# Sheet1.net
KiCad netlist of a schematic drawn in Altium Designer
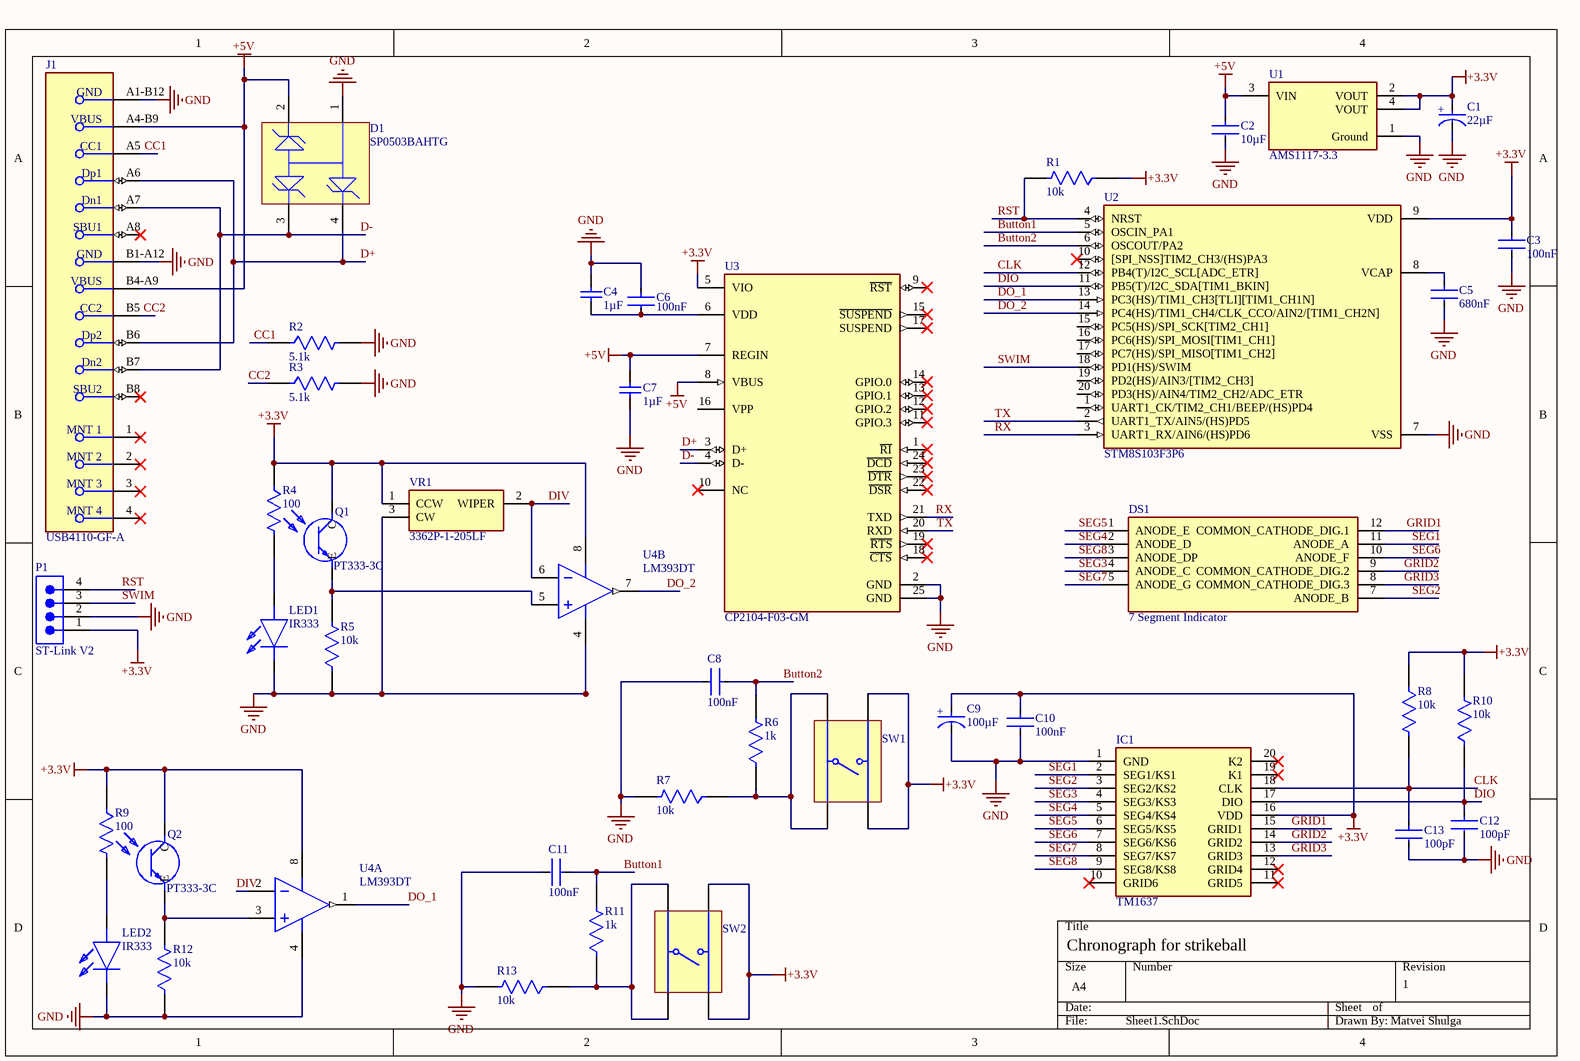
[diagram p0: Sheet1.SchDoc]

(export (version "E")
  (design (tool "Eeschema 10.0.6"))
  (components
    (comp (ref "C1")
      (value "22µF")
      (footprint "FP-TAJA-MFG")
      (description "Cap Tant Solid 22uF 10V A CASE 20%( 3.2 X 1.6 X 1.6mm) Inward L SMD 3216-18 3 Ohm 125C T/R")
      (fields (field (name "VOLTAGE") "10V") (field (name "TOLERANCE") "20%"))
      (libsource (lib "Matvey Shulga") (part "203bc49f2ac43e59fd269a8c329ed05"))
    )
    (comp (ref "C2")
      (value "10µF")
      (footprint "FP-GCJ31C-0_4-IPC_C")
      (description "Ceramic Capacitor, Ceramic, 35V, 10% +Tol, 10% -Tol, X7T, 22/-33% TC, 10uF, Surface Mount, 1206")
      (fields (field (name "VOLTAGE") "35V") (field (name "TOLERANCE") "10%"))
      (libsource (lib "Matvey Shulga") (part "02cd4be3c70576c341d710602a673aa"))
    )
    (comp (ref "C3")
      (value "100nF")
      (footprint "FP-1206-L_3_2_0_15-W_1_6-IPC_B")
      (fields (field (name "Comment") "UMK316B7104KLHT"))
      (libsource (lib "Matvey Shulga") (part "02cd4be3c70576c341d710602a673aa"))
    )
    (comp (ref "C4")
      (value "1µF")
      (footprint "CAPC1206(3216)130_M")
      (fields
        (field (name "VOLTAGE") "10V")
        (field (name "TOLERANCE") "5%")
        (field (name "Comment") "1206ZC105JAT2A")
      )
      (libsource (lib "Matvey Shulga") (part "CAP"))
    )
    (comp (ref "C5")
      (value "680nF")
      (footprint "FP-CC0805-0_85-IPC_A")
      (fields (field (name "Comment") "CC0805KKX7R6BB684"))
      (libsource (lib "Matvey Shulga") (part "11868f565c42a9108669ba33697ecf6"))
    )
    (comp (ref "C6")
      (value "100nF")
      (footprint "FP-1206-L_3_2_0_15-W_1_6-IPC_B")
      (fields (field (name "Comment") "UMK316B7104KLHT"))
      (libsource (lib "Matvey Shulga") (part "02cd4be3c70576c341d710602a673aa"))
    )
    (comp (ref "C7")
      (value "1µF")
      (footprint "CAPC1206(3216)130_M")
      (fields
        (field (name "VOLTAGE") "10V")
        (field (name "TOLERANCE") "5%")
        (field (name "Comment") "1206ZC105JAT2A")
      )
      (libsource (lib "Matvey Shulga") (part "CAP"))
    )
    (comp (ref "C8")
      (value "100nF")
      (footprint "FP-1206-L_3_2_0_15-W_1_6-IPC_B")
      (fields (field (name "Comment") "UMK316B7104KLHT"))
      (libsource (lib "Matvey Shulga") (part "02cd4be3c70576c341d710602a673aa"))
    )
    (comp (ref "C9")
      (value "100µF")
      (footprint "FP-TLJA-MFG")
      (description "Cap Tant Solid 100uF 6.3V A CASE 20% (3.2 X 1.6 X 1.6mm) Inward L SMD 3216-18 0.5 Ohm 125C T/R")
      (fields (field (name "VOLTAGE") "6.3V") (field (name "TOLERANCE") "20%"))
      (libsource (lib "Matvey Shulga") (part "a00bbbee19879c290e62620ae7e47b1"))
    )
    (comp (ref "C10")
      (value "100nF")
      (footprint "FP-1206-L_3_2_0_15-W_1_6-IPC_B")
      (fields (field (name "Comment") "UMK316B7104KLHT"))
      (libsource (lib "Matvey Shulga") (part "02cd4be3c70576c341d710602a673aa"))
    )
    (comp (ref "C11")
      (value "100nF")
      (footprint "FP-1206-L_3_2_0_15-W_1_6-IPC_B")
      (fields (field (name "Comment") "UMK316B7104KLHT"))
      (libsource (lib "Matvey Shulga") (part "02cd4be3c70576c341d710602a673aa"))
    )
    (comp (ref "C12")
      (value "100pF")
      (footprint "FP-1206-L_3_2_0_2-W_1_6_0-IPC_A")
      (fields (field (name "Comment") "12063A101KAT2A"))
      (libsource (lib "Matvey Shulga") (part "02cd4be3c70576c341d710602a673aa"))
    )
    (comp (ref "C13")
      (value "100pF")
      (footprint "FP-1206-L_3_2_0_2-W_1_6_0-IPC_A")
      (fields (field (name "Comment") "12063A101KAT2A"))
      (libsource (lib "Matvey Shulga") (part "02cd4be3c70576c341d710602a673aa"))
    )
    (comp (ref "D1")
      (value "SP0503BAHTG")
      (footprint "LFUS-SOT143-4_V")
      (description "SP050xBA Series 8.5 V 30 pF Triple Uni-Directional TVS Avalanche Diode-SOT143-4")
      (libsource (lib "Matvey Shulga") (part "LFUS-SP0503BAHTG-SOT143-4"))
    )
    (comp (ref "DS1")
      (value "7 Segment Indicator")
      (footprint "SamacSys:ELT315USOWAS530A3")
      (description "Display")
      (fields (field (name "MANUFACTURER") "Everlight") (field (name "PART NUMBER") "ELT-315USOWA/S530-A3"))
      (libsource (lib "*") (part "ELT-315USOWA_S530-A3"))
    )
    (comp (ref "IC1")
      (value "TM1637")
      (footprint "SamacSys:SOIC127P1045X280-20N")
      (description "Integrated Circuit")
      (fields
        (field (name "MANUFACTURER") "TITAN MICRO ELECTRONICS")
        (field (name "PART NUMBER") "TM1637 (SOP)")
      )
      (libsource (lib "*") (part "TM1637__SOP_"))
    )
    (comp (ref "J1")
      (value "USB4110-GF-A")
      (footprint "FP-USB4110-GF-A-MFG")
      (description "USB Connector, 16 Contact(s), Male, Right Angle, Surface Mount Terminal, Locking, Receptacle")
      (fields (field (name "VOLTAGE") "20V"))
      (libsource (lib "Matvey Shulga") (part "e23f2b38bb3c3f98e683ebab9ede730"))
    )
    (comp (ref "LED1")
      (value "IR333")
      (footprint "SamacSys:IR333H0A")
      (description "LED")
      (fields (field (name "MANUFACTURER") "Everlight") (field (name "PART NUMBER") "IR333/H0-A"))
      (libsource (lib "*") (part "IR333_H0-A"))
    )
    (comp (ref "LED2")
      (value "IR333")
      (footprint "SamacSys:IR333H0A")
      (description "LED")
      (fields (field (name "MANUFACTURER") "Everlight") (field (name "PART NUMBER") "IR333/H0-A"))
      (libsource (lib "*") (part "IR333_H0-A"))
    )
    (comp (ref "P1")
      (value "ST-Link V2")
      (footprint "61300411021")
      (libsource (lib "Matvey Shulga") (part "CMP-1502-01063-3"))
    )
    (comp (ref "Q1")
      (value "PT333-3C")
      (footprint "SamacSys:PT3333C")
      (description "Phototransistor")
      (fields (field (name "MANUFACTURER") "Everlight") (field (name "MOUSER PART NUMBER") "638-PT3333C"))
      (libsource (lib "*") (part "PT333-3C"))
    )
    (comp (ref "Q2")
      (value "PT333-3C")
      (footprint "SamacSys:PT3333C")
      (description "Phototransistor")
      (fields (field (name "MANUFACTURER") "Everlight") (field (name "MOUSER PART NUMBER") "638-PT3333C"))
      (libsource (lib "*") (part "PT333-3C"))
    )
    (comp (ref "R1")
      (value "10k")
      (footprint "FP-AC1206-IPC_A")
      (description "Res Thick Film 1206 10K Ohm 1% 0.25W(1/4W) ±100ppm/°C Pad SMD T/R Automotive AEC-Q200")
      (fields (field (name "TOLERANCE") "1%") (field (name "VOLTAGE") "200V"))
      (libsource (lib "Matvey Shulga") (part "1029c3af85768c4190bb7ad29bc67b5"))
    )
    (comp (ref "R2")
      (value "5.1k")
      (footprint "FP-ESR18-IPC_A")
      (description "Res Thick Film 1206 5.1K Ohm 1% 0.5W(1/2W) ±100ppm/C Pad SMD T/R Automotive AEC-Q200")
      (fields (field (name "TOLERANCE") "1%") (field (name "VOLTAGE") "200V"))
      (libsource (lib "Matvey Shulga") (part "1029c3af85768c4190bb7ad29bc67b5"))
    )
    (comp (ref "R3")
      (value "5.1k")
      (footprint "FP-ESR18-IPC_A")
      (description "Res Thick Film 1206 5.1K Ohm 1% 0.5W(1/2W) ±100ppm/C Pad SMD T/R Automotive AEC-Q200")
      (fields (field (name "TOLERANCE") "1%") (field (name "VOLTAGE") "200V"))
      (libsource (lib "Matvey Shulga") (part "1029c3af85768c4190bb7ad29bc67b5"))
    )
    (comp (ref "R4")
      (value "100")
      (footprint "FP-RC3216-IPC_B")
      (description "Res Thick Film 1206 100 Ohm 5% 1/4W ±100ppm/°C Molded SMD T/R")
      (fields (field (name "TOLERANCE") "5%") (field (name "VOLTAGE") "200V"))
      (libsource (lib "Matvey Shulga") (part "1029c3af85768c4190bb7ad29bc67b5"))
    )
    (comp (ref "R5")
      (value "10k")
      (footprint "FP-AC1206-IPC_A")
      (description "Res Thick Film 1206 10K Ohm 1% 0.25W(1/4W) ±100ppm/°C Pad SMD T/R Automotive AEC-Q200")
      (fields (field (name "TOLERANCE") "1%") (field (name "VOLTAGE") "200V"))
      (libsource (lib "Matvey Shulga") (part "1029c3af85768c4190bb7ad29bc67b5"))
    )
    (comp (ref "R6")
      (value "1k")
      (footprint "FP-RP732B-MFG")
      (description "Res Thin Film 1206 1K Ohm 0.1% 0.25W(1/4W) ±15ppm/C Pad SMD Cut Tape Medical")
      (fields (field (name "VOLTAGE") "25V") (field (name "TOLERANCE") "0.1%"))
      (libsource (lib "Matvey Shulga") (part "1029c3af85768c4190bb7ad29bc67b5"))
    )
    (comp (ref "R7")
      (value "10k")
      (footprint "FP-AC1206-IPC_A")
      (description "Res Thick Film 1206 10K Ohm 1% 0.25W(1/4W) ±100ppm/°C Pad SMD T/R Automotive AEC-Q200")
      (fields (field (name "TOLERANCE") "1%") (field (name "VOLTAGE") "200V"))
      (libsource (lib "Matvey Shulga") (part "1029c3af85768c4190bb7ad29bc67b5"))
    )
    (comp (ref "R8")
      (value "10k")
      (footprint "FP-AC1206-IPC_A")
      (description "Res Thick Film 1206 10K Ohm 1% 0.25W(1/4W) ±100ppm/°C Pad SMD T/R Automotive AEC-Q200")
      (fields (field (name "TOLERANCE") "1%") (field (name "VOLTAGE") "200V"))
      (libsource (lib "Matvey Shulga") (part "1029c3af85768c4190bb7ad29bc67b5"))
    )
    (comp (ref "R9")
      (value "100")
      (footprint "FP-RC3216-IPC_B")
      (description "Res Thick Film 1206 100 Ohm 5% 1/4W ±100ppm/°C Molded SMD T/R")
      (fields (field (name "TOLERANCE") "5%") (field (name "VOLTAGE") "200V"))
      (libsource (lib "Matvey Shulga") (part "1029c3af85768c4190bb7ad29bc67b5"))
    )
    (comp (ref "R10")
      (value "10k")
      (footprint "FP-AC1206-IPC_A")
      (description "Res Thick Film 1206 10K Ohm 1% 0.25W(1/4W) ±100ppm/°C Pad SMD T/R Automotive AEC-Q200")
      (fields (field (name "TOLERANCE") "1%") (field (name "VOLTAGE") "200V"))
      (libsource (lib "Matvey Shulga") (part "1029c3af85768c4190bb7ad29bc67b5"))
    )
    (comp (ref "R11")
      (value "1k")
      (footprint "FP-RP732B-MFG")
      (description "Res Thin Film 1206 1K Ohm 0.1% 0.25W(1/4W) ±15ppm/C Pad SMD Cut Tape Medical")
      (fields (field (name "VOLTAGE") "25V") (field (name "TOLERANCE") "0.1%"))
      (libsource (lib "Matvey Shulga") (part "1029c3af85768c4190bb7ad29bc67b5"))
    )
    (comp (ref "R12")
      (value "10k")
      (footprint "FP-AC1206-IPC_A")
      (description "Res Thick Film 1206 10K Ohm 1% 0.25W(1/4W) ±100ppm/°C Pad SMD T/R Automotive AEC-Q200")
      (fields (field (name "TOLERANCE") "1%") (field (name "VOLTAGE") "200V"))
      (libsource (lib "Matvey Shulga") (part "1029c3af85768c4190bb7ad29bc67b5"))
    )
    (comp (ref "R13")
      (value "10k")
      (footprint "FP-AC1206-IPC_A")
      (description "Res Thick Film 1206 10K Ohm 1% 0.25W(1/4W) ±100ppm/°C Pad SMD T/R Automotive AEC-Q200")
      (fields (field (name "TOLERANCE") "1%") (field (name "VOLTAGE") "200V"))
      (libsource (lib "Matvey Shulga") (part "1029c3af85768c4190bb7ad29bc67b5"))
    )
    (comp (ref "SW1")
      (value "FSM4JSMATR")
      (footprint "TECO-FSM4JSMATR_V")
      (libsource (lib "Matvey Shulga") (part "SW-SPST-4_A"))
    )
    (comp (ref "SW2")
      (value "FSM4JSMATR")
      (footprint "TECO-FSM4JSMATR_V")
      (libsource (lib "Matvey Shulga") (part "SW-SPST-4_A"))
    )
    (comp (ref "U1")
      (value "AMS1117-3.3")
      (footprint "FP-AMS1117-IPC_B")
      (description "Fixed Positive LDO Regulator, 3.3V, 1.3V Dropout, PDSO3")
      (libsource (lib "Matvey Shulga") (part "8bdbb5f8e77002000e30dd2845d0354"))
    )
    (comp (ref "U2")
      (value "STM8S103F3P6")
      (footprint "SOP65P640X120-20N")
      (description "STM8 series Microcontroller IC 8-Bit 16MHz 8KB (8K x 8) FLASH 20-TSSOP")
      (fields (field (name "MF") "STMicroelectronics"))
      (libsource (lib "Matvey Shulga") (part "STM8S103F3P6"))
    )
    (comp (ref "U3")
      (value "CP2104-F03-GM")
      (footprint "FP-CP2104-F03-GM-MFG")
      (description "USB-to-UART 1-CH 576byte FIFO 3.3V Automotive 24-Pin QFN EP Tube")
      (libsource (lib "Matvey Shulga") (part "36aa9e967c7f1036f799a443da3d357"))
    )
    (comp (ref "U4")
      (value "LM393DT")
      (footprint "STM-SO-8_D_L")
      (description "Comparator, 2 Func, 9000uV Offset-Max, 1300ns Response Time, BIPolar, PDSO8")
      (libsource (lib "Matvey Shulga") (part "STM-LM393-SO8"))
    )
    (comp (ref "VR1")
      (value "3362P-1-205LF")
      (footprint "SamacSys:3362P1205LF")
      (description "Variable Resistor")
      (fields (field (name "MANUFACTURER") "Bourns") (field (name "MOUSER PART NUMBER") "652-3362P-1-205LF"))
      (libsource (lib "*") (part "3362P-1-205LF"))
    )
  )
  (nets
    (net (code "1") (name "+3.3V") (class "Default")
      (node (ref "C1") (pin "2") (pinfunction "A_2") (pintype "passive"))
      (node (ref "C10") (pin "1") (pinfunction "1_1") (pintype "passive"))
      (node (ref "C3") (pin "1") (pinfunction "1_1") (pintype "passive"))
      (node (ref "C9") (pin "2") (pinfunction "A_2") (pintype "passive"))
      (node (ref "IC1") (pin "16") (pinfunction "VDD_16") (pintype "passive"))
      (node (ref "P1") (pin "1") (pinfunction "1_1") (pintype "passive"))
      (node (ref "Q1") (pin "2") (pinfunction "C_2") (pintype "passive"))
      (node (ref "Q2") (pin "2") (pinfunction "C_2") (pintype "passive"))
      (node (ref "R1") (pin "1") (pinfunction "1_1") (pintype "passive"))
      (node (ref "R10") (pin "2") (pinfunction "2_2") (pintype "passive"))
      (node (ref "R4") (pin "1") (pinfunction "1_1") (pintype "passive"))
      (node (ref "R8") (pin "1") (pinfunction "1_1") (pintype "passive"))
      (node (ref "R9") (pin "1") (pinfunction "1_1") (pintype "passive"))
      (node (ref "SW1") (pin "3") (pinfunction "3_3") (pintype "passive"))
      (node (ref "SW1") (pin "4") (pinfunction "4_4") (pintype "passive"))
      (node (ref "SW2") (pin "3") (pinfunction "3_3") (pintype "passive"))
      (node (ref "SW2") (pin "4") (pinfunction "4_4") (pintype "passive"))
      (node (ref "U1") (pin "2") (pinfunction "VOUT_2") (pintype "passive"))
      (node (ref "U1") (pin "4") (pinfunction "VOUT_4") (pintype "passive"))
      (node (ref "U2") (pin "9") (pinfunction "VDD_9") (pintype "power_in"))
      (node (ref "U3") (pin "5") (pinfunction "VIO_5") (pintype "power_in"))
      (node (ref "U4") (pin "8") (pinfunction "VCC+_8") (pintype "power_in"))
      (node (ref "VR1") (pin "1") (pinfunction "CCW_1") (pintype "passive"))
    )
    (net (code "2") (name "+5V") (class "Default")
      (node (ref "C2") (pin "1") (pinfunction "1_1") (pintype "passive"))
      (node (ref "C7") (pin "2") (pinfunction "2_2") (pintype "passive"))
      (node (ref "D1") (pin "2") (pinfunction "2_2") (pintype "passive"))
      (node (ref "J1") (pin "A4-B9") (pinfunction "VBUS_A4-B9") (pintype "power_in"))
      (node (ref "J1") (pin "B4-A9") (pinfunction "VBUS_B4-A9") (pintype "power_in"))
      (node (ref "U1") (pin "3") (pinfunction "VIN_3") (pintype "power_in"))
      (node (ref "U3") (pin "7") (pinfunction "REGIN_7") (pintype "power_in"))
      (node (ref "U3") (pin "8") (pinfunction "VBUS_8") (pintype "input"))
    )
    (net (code "3") (name "/Button1") (class "Default")
      (node (ref "C11") (pin "1") (pinfunction "1_1") (pintype "passive"))
      (node (ref "R11") (pin "2") (pinfunction "2_2") (pintype "passive"))
      (node (ref "U2") (pin "5") (pinfunction "OSCIN_PA1_5") (pintype "bidirectional"))
    )
    (net (code "4") (name "/Button2") (class "Default")
      (node (ref "C8") (pin "1") (pinfunction "1_1") (pintype "passive"))
      (node (ref "R6") (pin "2") (pinfunction "2_2") (pintype "passive"))
      (node (ref "U2") (pin "6") (pinfunction "OSCOUT/PA2_6") (pintype "bidirectional"))
    )
    (net (code "5") (name "/CC1") (class "Default")
      (node (ref "J1") (pin "A5") (pinfunction "CC1_A5") (pintype "power_in"))
      (node (ref "R2") (pin "1") (pinfunction "1_1") (pintype "passive"))
    )
    (net (code "6") (name "/CC2") (class "Default")
      (node (ref "J1") (pin "B5") (pinfunction "CC2_B5") (pintype "power_in"))
      (node (ref "R3") (pin "1") (pinfunction "1_1") (pintype "passive"))
    )
    (net (code "7") (name "/CLK") (class "Default")
      (node (ref "C13") (pin "1") (pinfunction "1_1") (pintype "passive"))
      (node (ref "IC1") (pin "18") (pinfunction "CLK_18") (pintype "passive"))
      (node (ref "R8") (pin "2") (pinfunction "2_2") (pintype "passive"))
      (node (ref "U2") (pin "12") (pinfunction "PB4(T)/I2C_SCL[ADC_ETR]_12") (pintype "bidirectional"))
    )
    (net (code "8") (name "/D+") (class "Default")
      (node (ref "D1") (pin "4") (pinfunction "4_4") (pintype "passive"))
      (node (ref "J1") (pin "A6") (pinfunction "Dp1_A6") (pintype "bidirectional"))
      (node (ref "J1") (pin "B6") (pinfunction "Dp2_B6") (pintype "bidirectional"))
      (node (ref "U3") (pin "3") (pinfunction "D+_3") (pintype "bidirectional"))
    )
    (net (code "9") (name "/D-") (class "Default")
      (node (ref "D1") (pin "3") (pinfunction "3_3") (pintype "passive"))
      (node (ref "J1") (pin "A7") (pinfunction "Dn1_A7") (pintype "bidirectional"))
      (node (ref "J1") (pin "B7") (pinfunction "Dn2_B7") (pintype "bidirectional"))
      (node (ref "U3") (pin "4") (pinfunction "D-_4") (pintype "bidirectional"))
    )
    (net (code "10") (name "/DIO") (class "Default")
      (node (ref "C12") (pin "1") (pinfunction "1_1") (pintype "passive"))
      (node (ref "IC1") (pin "17") (pinfunction "DIO_17") (pintype "passive"))
      (node (ref "R10") (pin "1") (pinfunction "1_1") (pintype "passive"))
      (node (ref "U2") (pin "11") (pinfunction "PB5(T)/I2C_SDA[TIM1_BKIN]_11") (pintype "bidirectional"))
    )
    (net (code "11") (name "/DIV") (class "Default")
      (node (ref "U4") (pin "2") (pinfunction "IN1-_2") (pintype "passive"))
      (node (ref "U4") (pin "6") (pinfunction "IN2-_6") (pintype "input"))
      (node (ref "VR1") (pin "2") (pinfunction "WIPER_2") (pintype "passive"))
    )
    (net (code "12") (name "/DO_1") (class "Default")
      (node (ref "U2") (pin "13") (pinfunction "PC3(HS)/TIM1_CH3[TLI][TIM1_CH1N]_13") (pintype "input"))
      (node (ref "U4") (pin "1") (pinfunction "OUT1_1") (pintype "output"))
    )
    (net (code "13") (name "/DO_2") (class "Default")
      (node (ref "U2") (pin "14") (pinfunction "PC4(HS)/TIM1_CH4/CLK_CCO/AIN2/[TIM1_CH2N]_14") (pintype "input"))
      (node (ref "U4") (pin "7") (pinfunction "OUT2_7") (pintype "output"))
    )
    (net (code "14") (name "/GRID1") (class "Default")
      (node (ref "DS1") (pin "12") (pinfunction "COMMON_CATHODE_DIG.1_12") (pintype "passive"))
      (node (ref "IC1") (pin "15") (pinfunction "GRID1_15") (pintype "passive"))
    )
    (net (code "15") (name "/GRID2") (class "Default")
      (node (ref "DS1") (pin "9") (pinfunction "COMMON_CATHODE_DIG.2_9") (pintype "passive"))
      (node (ref "IC1") (pin "14") (pinfunction "GRID2_14") (pintype "passive"))
    )
    (net (code "16") (name "/GRID3") (class "Default")
      (node (ref "DS1") (pin "8") (pinfunction "COMMON_CATHODE_DIG.3_8") (pintype "passive"))
      (node (ref "IC1") (pin "13") (pinfunction "GRID3_13") (pintype "passive"))
    )
    (net (code "17") (name "/RST") (class "Default")
      (node (ref "P1") (pin "4") (pinfunction "4_4") (pintype "passive"))
      (node (ref "R1") (pin "2") (pinfunction "2_2") (pintype "passive"))
      (node (ref "U2") (pin "4") (pinfunction "NRST_4") (pintype "bidirectional"))
    )
    (net (code "18") (name "/RX") (class "Default")
      (node (ref "U2") (pin "3") (pinfunction "UART1_RX/AIN6/(HS)PD6_3") (pintype "input"))
      (node (ref "U3") (pin "21") (pinfunction "TXD_21") (pintype "output"))
    )
    (net (code "19") (name "/SEG1") (class "Default")
      (node (ref "DS1") (pin "11") (pinfunction "ANODE_A_11") (pintype "passive"))
      (node (ref "IC1") (pin "2") (pinfunction "SEG1/KS1_2") (pintype "passive"))
    )
    (net (code "20") (name "/SEG2") (class "Default")
      (node (ref "DS1") (pin "7") (pinfunction "ANODE_B_7") (pintype "passive"))
      (node (ref "IC1") (pin "3") (pinfunction "SEG2/KS2_3") (pintype "passive"))
    )
    (net (code "21") (name "/SEG3") (class "Default")
      (node (ref "DS1") (pin "4") (pinfunction "ANODE_C_4") (pintype "passive"))
      (node (ref "IC1") (pin "4") (pinfunction "SEG3/KS3_4") (pintype "passive"))
    )
    (net (code "22") (name "/SEG4") (class "Default")
      (node (ref "DS1") (pin "2") (pinfunction "ANODE_D_2") (pintype "passive"))
      (node (ref "IC1") (pin "5") (pinfunction "SEG4/KS4_5") (pintype "passive"))
    )
    (net (code "23") (name "/SEG5") (class "Default")
      (node (ref "DS1") (pin "1") (pinfunction "ANODE_E_1") (pintype "passive"))
      (node (ref "IC1") (pin "6") (pinfunction "SEG5/KS5_6") (pintype "passive"))
    )
    (net (code "24") (name "/SEG6") (class "Default")
      (node (ref "DS1") (pin "10") (pinfunction "ANODE_F_10") (pintype "passive"))
      (node (ref "IC1") (pin "7") (pinfunction "SEG6/KS6_7") (pintype "passive"))
    )
    (net (code "25") (name "/SEG7") (class "Default")
      (node (ref "DS1") (pin "5") (pinfunction "ANODE_G_5") (pintype "passive"))
      (node (ref "IC1") (pin "8") (pinfunction "SEG7/KS7_8") (pintype "passive"))
    )
    (net (code "26") (name "/SEG8") (class "Default")
      (node (ref "DS1") (pin "3") (pinfunction "ANODE_DP_3") (pintype "passive"))
      (node (ref "IC1") (pin "9") (pinfunction "SEG8/KS8_9") (pintype "passive"))
    )
    (net (code "27") (name "/SWIM") (class "Default")
      (node (ref "P1") (pin "3") (pinfunction "3_3") (pintype "passive"))
      (node (ref "U2") (pin "18") (pinfunction "PD1(HS)/SWIM_18") (pintype "bidirectional"))
    )
    (net (code "28") (name "/TX") (class "Default")
      (node (ref "U2") (pin "2") (pinfunction "UART1_TX/AIN5/(HS)PD5_2") (pintype "output"))
      (node (ref "U3") (pin "20") (pinfunction "RXD_20") (pintype "input"))
    )
    (net (code "29") (name "GND") (class "Default")
      (node (ref "C1") (pin "1") (pinfunction "C_1") (pintype "passive"))
      (node (ref "C10") (pin "2") (pinfunction "2_2") (pintype "passive"))
      (node (ref "C11") (pin "2") (pinfunction "2_2") (pintype "passive"))
      (node (ref "C12") (pin "2") (pinfunction "2_2") (pintype "passive"))
      (node (ref "C13") (pin "2") (pinfunction "2_2") (pintype "passive"))
      (node (ref "C2") (pin "2") (pinfunction "2_2") (pintype "passive"))
      (node (ref "C3") (pin "2") (pinfunction "2_2") (pintype "passive"))
      (node (ref "C4") (pin "2") (pinfunction "2_2") (pintype "passive"))
      (node (ref "C5") (pin "2") (pinfunction "2_2") (pintype "passive"))
      (node (ref "C6") (pin "1") (pinfunction "1_1") (pintype "passive"))
      (node (ref "C7") (pin "1") (pinfunction "1_1") (pintype "passive"))
      (node (ref "C8") (pin "2") (pinfunction "2_2") (pintype "passive"))
      (node (ref "C9") (pin "1") (pinfunction "C_1") (pintype "passive"))
      (node (ref "D1") (pin "1") (pinfunction "1_1") (pintype "passive"))
      (node (ref "IC1") (pin "1") (pinfunction "GND_1") (pintype "passive"))
      (node (ref "J1") (pin "A1-B12") (pinfunction "GND_A1-B12") (pintype "passive"))
      (node (ref "J1") (pin "B1-A12") (pinfunction "GND_B1-A12") (pintype "passive"))
      (node (ref "LED1") (pin "2") (pinfunction "K_2") (pintype "passive"))
      (node (ref "LED2") (pin "2") (pinfunction "K_2") (pintype "passive"))
      (node (ref "P1") (pin "2") (pinfunction "2_2") (pintype "passive"))
      (node (ref "R12") (pin "1") (pinfunction "1_1") (pintype "passive"))
      (node (ref "R13") (pin "2") (pinfunction "2_2") (pintype "passive"))
      (node (ref "R2") (pin "2") (pinfunction "2_2") (pintype "passive"))
      (node (ref "R3") (pin "2") (pinfunction "2_2") (pintype "passive"))
      (node (ref "R5") (pin "1") (pinfunction "1_1") (pintype "passive"))
      (node (ref "R7") (pin "2") (pinfunction "2_2") (pintype "passive"))
      (node (ref "U1") (pin "1") (pinfunction "Ground_1") (pintype "power_in"))
      (node (ref "U2") (pin "7") (pinfunction "VSS_7") (pintype "power_in"))
      (node (ref "U3") (pin "2") (pinfunction "GND_2") (pintype "power_in"))
      (node (ref "U3") (pin "25") (pinfunction "GND_25") (pintype "power_in"))
      (node (ref "U4") (pin "4") (pinfunction "VCC-_4") (pintype "power_in"))
      (node (ref "VR1") (pin "3") (pinfunction "CW_3") (pintype "passive"))
    )
    (net (code "30") (name "Net-(LED1-A)") (class "Default")
      (node (ref "LED1") (pin "1") (pinfunction "A_1") (pintype "passive"))
      (node (ref "R4") (pin "2") (pinfunction "2_2") (pintype "passive"))
    )
    (net (code "31") (name "Net-(LED2-A)") (class "Default")
      (node (ref "LED2") (pin "1") (pinfunction "A_1") (pintype "passive"))
      (node (ref "R9") (pin "2") (pinfunction "2_2") (pintype "passive"))
    )
    (net (code "32") (name "Net-(Q1-E)") (class "Default")
      (node (ref "Q1") (pin "1") (pinfunction "E_1") (pintype "passive"))
      (node (ref "R5") (pin "2") (pinfunction "2_2") (pintype "passive"))
      (node (ref "U4") (pin "5") (pinfunction "IN2+_5") (pintype "input"))
    )
    (net (code "33") (name "Net-(Q2-E)") (class "Default")
      (node (ref "Q2") (pin "1") (pinfunction "E_1") (pintype "passive"))
      (node (ref "R12") (pin "2") (pinfunction "2_2") (pintype "passive"))
      (node (ref "U4") (pin "3") (pinfunction "IN1+_3") (pintype "passive"))
    )
    (net (code "34") (name "Net-(R6-Pad1)") (class "Default")
      (node (ref "R6") (pin "1") (pinfunction "1_1") (pintype "passive"))
      (node (ref "R7") (pin "1") (pinfunction "1_1") (pintype "passive"))
      (node (ref "SW1") (pin "1") (pinfunction "1_1") (pintype "passive"))
      (node (ref "SW1") (pin "2") (pinfunction "2_2") (pintype "passive"))
    )
    (net (code "35") (name "Net-(R11-Pad1)") (class "Default")
      (node (ref "R11") (pin "1") (pinfunction "1_1") (pintype "passive"))
      (node (ref "R13") (pin "1") (pinfunction "1_1") (pintype "passive"))
      (node (ref "SW2") (pin "1") (pinfunction "1_1") (pintype "passive"))
      (node (ref "SW2") (pin "2") (pinfunction "2_2") (pintype "passive"))
    )
    (net (code "36") (name "Net-(U2-VCAP)") (class "Default")
      (node (ref "C5") (pin "1") (pinfunction "1_1") (pintype "passive"))
      (node (ref "U2") (pin "8") (pinfunction "VCAP_8") (pintype "passive"))
    )
    (net (code "37") (name "Net-(U3-VDD)") (class "Default")
      (node (ref "C4") (pin "1") (pinfunction "1_1") (pintype "passive"))
      (node (ref "C6") (pin "2") (pinfunction "2_2") (pintype "passive"))
      (node (ref "U3") (pin "6") (pinfunction "VDD_6") (pintype "power_in"))
    )
    (net (code "38") (name "unconnected-(IC1-GRID4-Pad12)") (class "Default")
      (node (ref "IC1") (pin "12") (pinfunction "GRID4_12") (pintype "passive+no_connect"))
    )
    (net (code "39") (name "unconnected-(IC1-GRID5-Pad11)") (class "Default")
      (node (ref "IC1") (pin "11") (pinfunction "GRID5_11") (pintype "passive+no_connect"))
    )
    (net (code "40") (name "unconnected-(IC1-GRID6-Pad10)") (class "Default")
      (node (ref "IC1") (pin "10") (pinfunction "GRID6_10") (pintype "passive+no_connect"))
    )
    (net (code "41") (name "unconnected-(IC1-K1-Pad19)") (class "Default")
      (node (ref "IC1") (pin "19") (pinfunction "K1_19") (pintype "passive+no_connect"))
    )
    (net (code "42") (name "unconnected-(IC1-K2-Pad20)") (class "Default")
      (node (ref "IC1") (pin "20") (pinfunction "K2_20") (pintype "passive+no_connect"))
    )
    (net (code "43") (name "unconnected-(J1-MNT_1-Pad1)") (class "Default")
      (node (ref "J1") (pin "1") (pinfunction "MNT_1_1") (pintype "passive+no_connect"))
    )
    (net (code "44") (name "unconnected-(J1-MNT_2-Pad2)") (class "Default")
      (node (ref "J1") (pin "2") (pinfunction "MNT_2_2") (pintype "passive+no_connect"))
    )
    (net (code "45") (name "unconnected-(J1-MNT_3-Pad3)") (class "Default")
      (node (ref "J1") (pin "3") (pinfunction "MNT_3_3") (pintype "passive+no_connect"))
    )
    (net (code "46") (name "unconnected-(J1-MNT_4-Pad4)") (class "Default")
      (node (ref "J1") (pin "4") (pinfunction "MNT_4_4") (pintype "passive+no_connect"))
    )
    (net (code "47") (name "unconnected-(J1-SBU1-PadA8)") (class "Default")
      (node (ref "J1") (pin "A8") (pinfunction "SBU1_A8") (pintype "bidirectional+no_connect"))
    )
    (net (code "48") (name "unconnected-(J1-SBU2-PadB8)") (class "Default")
      (node (ref "J1") (pin "B8") (pinfunction "SBU2_B8") (pintype "bidirectional+no_connect"))
    )
    (net (code "49") (name "unconnected-(U2-PC5(HS){slash}SPI_SCK[TIM2_CH1]-Pad15)") (class "Default")
      (node (ref "U2") (pin "15") (pinfunction "PC5(HS)/SPI_SCK[TIM2_CH1]_15") (pintype "bidirectional"))
    )
    (net (code "50") (name "unconnected-(U2-PC6(HS){slash}SPI_MOSI[TIM1_CH1]-Pad16)") (class "Default")
      (node (ref "U2") (pin "16") (pinfunction "PC6(HS)/SPI_MOSI[TIM1_CH1]_16") (pintype "bidirectional"))
    )
    (net (code "51") (name "unconnected-(U2-PC7(HS){slash}SPI_MISO[TIM1_CH2]-Pad17)") (class "Default")
      (node (ref "U2") (pin "17") (pinfunction "PC7(HS)/SPI_MISO[TIM1_CH2]_17") (pintype "bidirectional"))
    )
    (net (code "52") (name "unconnected-(U2-PD2(HS){slash}AIN3{slash}[TIM2_CH3]-Pad19)") (class "Default")
      (node (ref "U2") (pin "19") (pinfunction "PD2(HS)/AIN3/[TIM2_CH3]_19") (pintype "bidirectional"))
    )
    (net (code "53") (name "unconnected-(U2-PD3(HS){slash}AIN4{slash}TIM2_CH2{slash}ADC_ETR-Pad20)") (class "Default")
      (node (ref "U2") (pin "20") (pinfunction "PD3(HS)/AIN4/TIM2_CH2/ADC_ETR_20") (pintype "bidirectional"))
    )
    (net (code "54") (name "unconnected-(U2-UART1_CK{slash}TIM2_CH1{slash}BEEP{slash}(HS)PD4-Pad1)") (class "Default")
      (node (ref "U2") (pin "1") (pinfunction "UART1_CK/TIM2_CH1/BEEP/(HS)PD4_1") (pintype "bidirectional"))
    )
    (net (code "55") (name "unconnected-(U2-[SPI_NSS]TIM2_CH3{slash}(HS)PA3-Pad10)") (class "Default")
      (node (ref "U2") (pin "10") (pinfunction "[SPI_NSS]TIM2_CH3/(HS)PA3_10") (pintype "bidirectional+no_connect"))
    )
    (net (code "56") (name "unconnected-(U3-GPIO.0-Pad14)") (class "Default")
      (node (ref "U3") (pin "14") (pinfunction "GPIO.0_14") (pintype "bidirectional+no_connect"))
    )
    (net (code "57") (name "unconnected-(U3-GPIO.1-Pad13)") (class "Default")
      (node (ref "U3") (pin "13") (pinfunction "GPIO.1_13") (pintype "bidirectional+no_connect"))
    )
    (net (code "58") (name "unconnected-(U3-GPIO.2-Pad12)") (class "Default")
      (node (ref "U3") (pin "12") (pinfunction "GPIO.2_12") (pintype "bidirectional+no_connect"))
    )
    (net (code "59") (name "unconnected-(U3-GPIO.3-Pad11)") (class "Default")
      (node (ref "U3") (pin "11") (pinfunction "GPIO.3_11") (pintype "bidirectional+no_connect"))
    )
    (net (code "60") (name "unconnected-(U3-NC-Pad10)") (class "Default")
      (node (ref "U3") (pin "10") (pinfunction "NC_10") (pintype "passive+no_connect"))
    )
    (net (code "61") (name "unconnected-(U3-SUSPEND-Pad17)") (class "Default")
      (node (ref "U3") (pin "17") (pinfunction "SUSPEND_17") (pintype "output+no_connect"))
    )
    (net (code "62") (name "unconnected-(U3-VPP-Pad16)") (class "Default")
      (node (ref "U3") (pin "16") (pinfunction "VPP_16") (pintype "passive"))
    )
    (net (code "63") (name "unconnected-(U3-~{CTS}-Pad18)") (class "Default")
      (node (ref "U3") (pin "18") (pinfunction "~{CTS}_18") (pintype "input+no_connect"))
    )
    (net (code "64") (name "unconnected-(U3-~{DCD}-Pad24)") (class "Default")
      (node (ref "U3") (pin "24") (pinfunction "~{DCD}_24") (pintype "input+no_connect"))
    )
    (net (code "65") (name "unconnected-(U3-~{DSR}-Pad22)") (class "Default")
      (node (ref "U3") (pin "22") (pinfunction "~{DSR}_22") (pintype "input+no_connect"))
    )
    (net (code "66") (name "unconnected-(U3-~{DTR}-Pad23)") (class "Default")
      (node (ref "U3") (pin "23") (pinfunction "~{DTR}_23") (pintype "output+no_connect"))
    )
    (net (code "67") (name "unconnected-(U3-~{RI}-Pad1)") (class "Default")
      (node (ref "U3") (pin "1") (pinfunction "~{RI}_1") (pintype "input+no_connect"))
    )
    (net (code "68") (name "unconnected-(U3-~{RST}-Pad9)") (class "Default")
      (node (ref "U3") (pin "9") (pinfunction "~{RST}_9") (pintype "bidirectional+no_connect"))
    )
    (net (code "69") (name "unconnected-(U3-~{RTS}-Pad19)") (class "Default")
      (node (ref "U3") (pin "19") (pinfunction "~{RTS}_19") (pintype "output+no_connect"))
    )
    (net (code "70") (name "unconnected-(U3-~{SUSPEND}-Pad15)") (class "Default")
      (node (ref "U3") (pin "15") (pinfunction "~{SUSPEND}_15") (pintype "output+no_connect"))
    )
  )
)
